# UPS_Module.net
KiCad netlist of a schematic drawn in Altium Designer
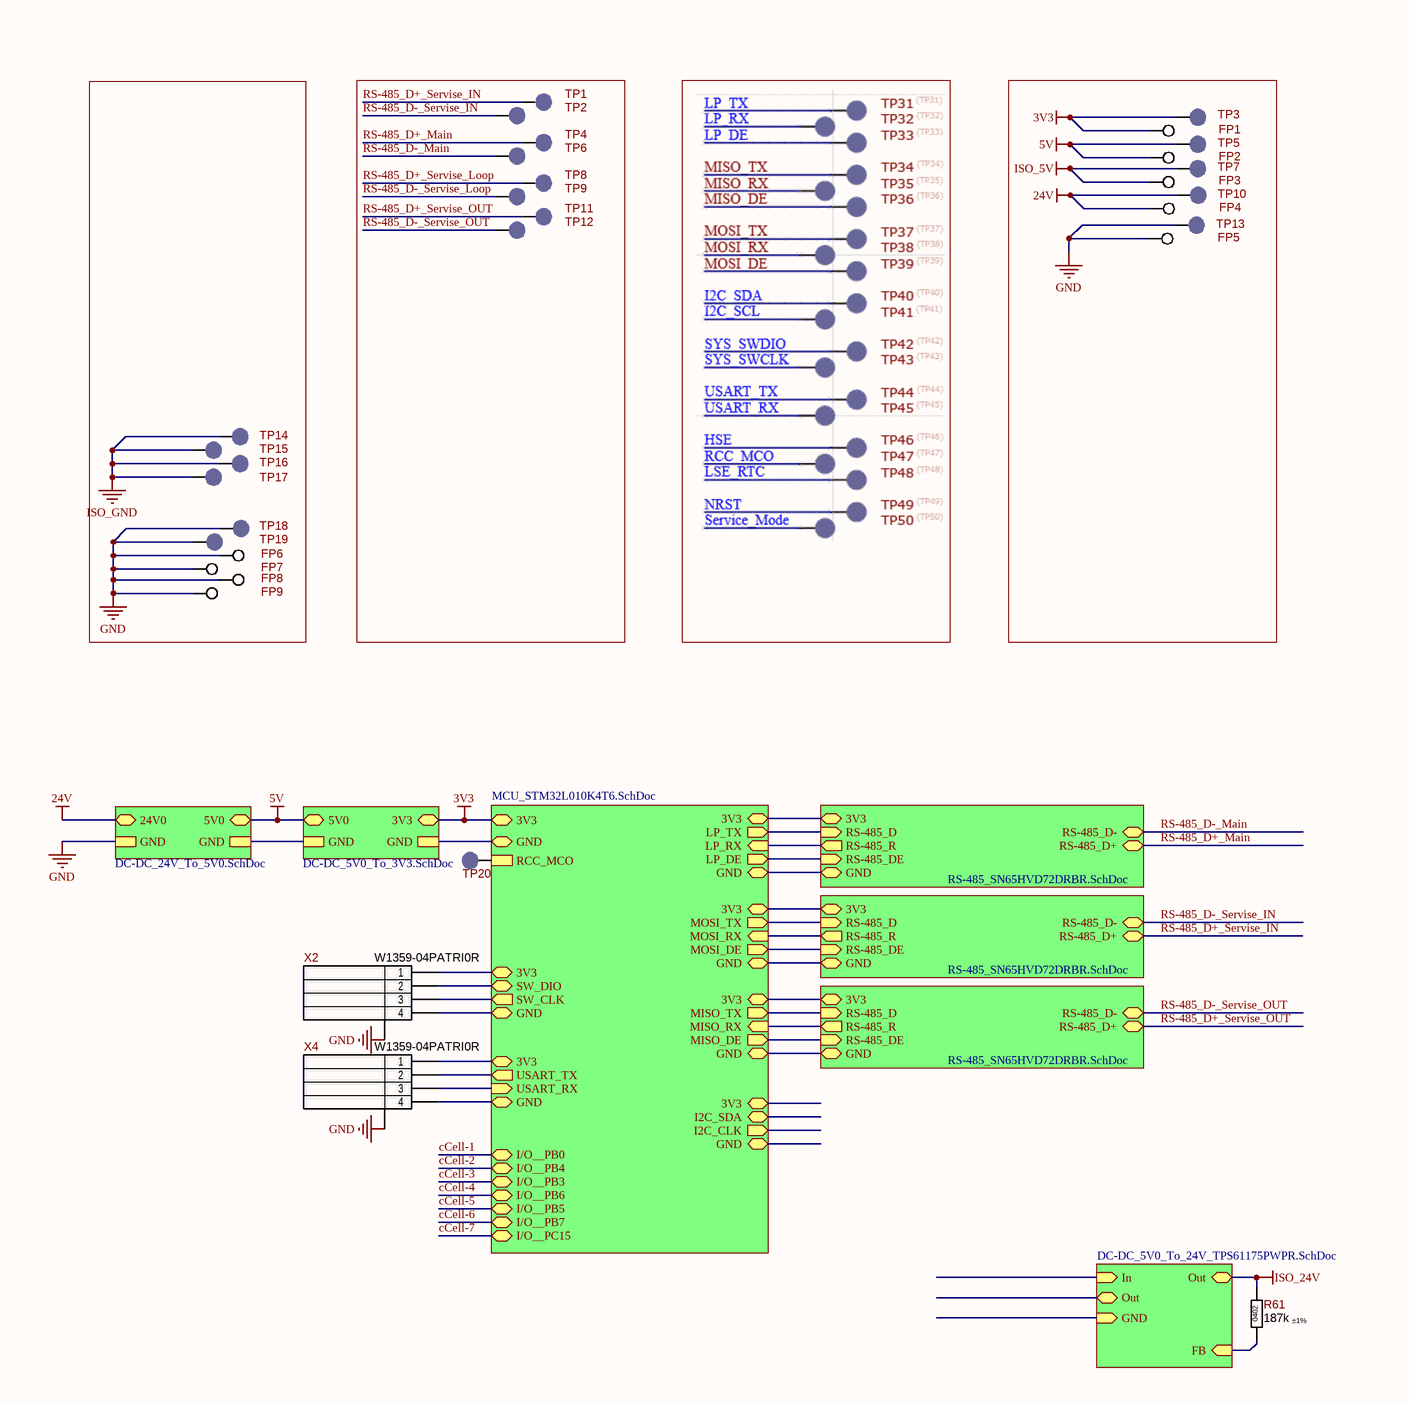
[diagram p0: UPS_Module.SchDoc, left]
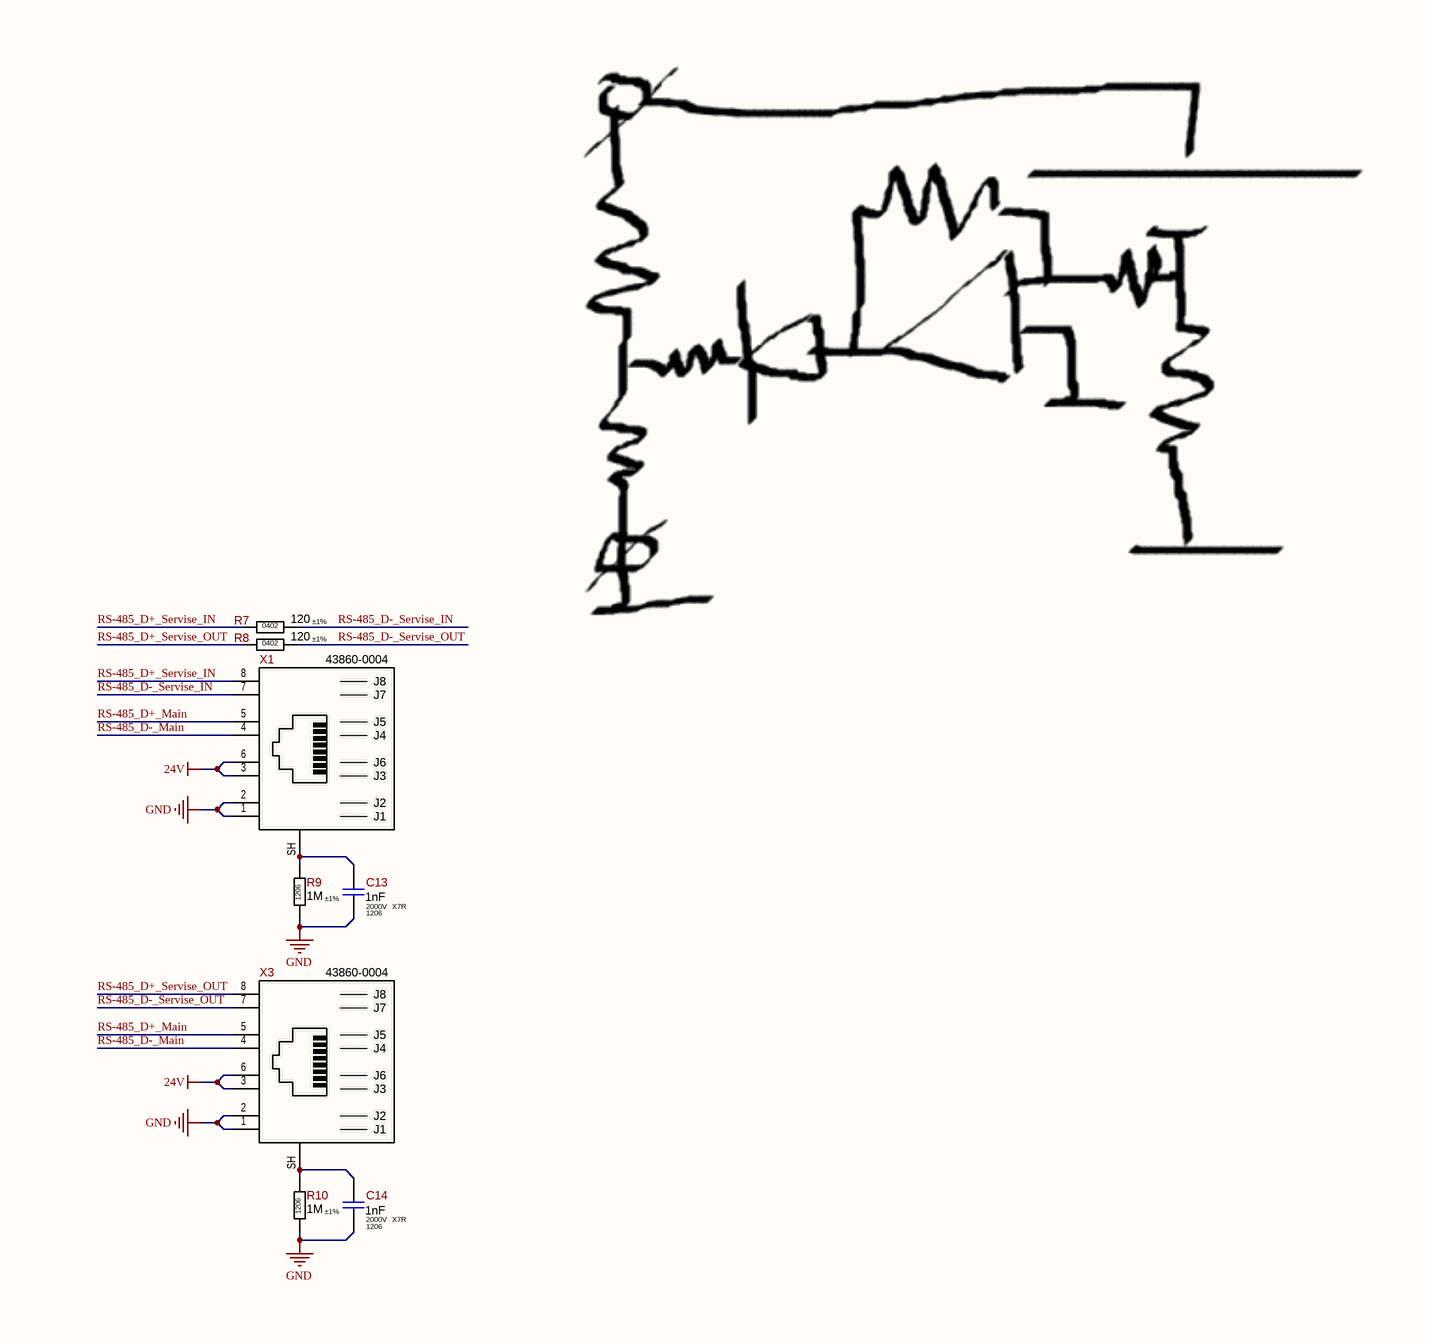
[diagram p1: UPS_Module.SchDoc, right]

(export (version "E")
  (design (tool "Eeschema 10.0.6"))
  (components
    (comp (ref "C13")
      (value "1nF")
      (footprint "CAP-1206(3216)X125T20")
      (description "1nF 2000V X7R ±10% 1206 Ceramic Capacitor RoHS")
      (fields
        (field (name "PACKAGE") "1206")
        (field (name "VOLTAGE") "2000V")
        (field (name "DIELECTRIC TYPE") "X7R")
        (field (name "PART NUMBER") "CC1206KKX7RDBB102")
        (field (name "MANUFACTURER") "Yageo")
      )
      (libsource (lib "EL.XXX.T01") (part "Capacitor-NonPolar"))
    )
    (comp (ref "C14")
      (value "1nF")
      (footprint "CAP-1206(3216)X125T20")
      (description "1nF 2000V X7R ±10% 1206 Ceramic Capacitor RoHS")
      (fields
        (field (name "PACKAGE") "1206")
        (field (name "VOLTAGE") "2000V")
        (field (name "DIELECTRIC TYPE") "X7R")
        (field (name "PART NUMBER") "CC1206KKX7RDBB102")
        (field (name "MANUFACTURER") "Yageo")
      )
      (libsource (lib "EL.XXX.T01") (part "Capacitor-NonPolar"))
    )
    (comp (ref "FP1")
      (value "PAD-1.1mm")
      (footprint "PAD-1.1mm")
      (description "1.1mm Pad for Plug-In or Receptacle")
      (fields (field (name "MANUFACTURER") "NONE"))
      (libsource (lib "EL.XXX.T01") (part "Pad"))
    )
    (comp (ref "FP2")
      (value "PAD-1.1mm")
      (footprint "PAD-1.1mm")
      (description "1.1mm Pad for Plug-In or Receptacle")
      (fields (field (name "MANUFACTURER") "NONE"))
      (libsource (lib "EL.XXX.T01") (part "Pad"))
    )
    (comp (ref "FP3")
      (value "PAD-1.1mm")
      (footprint "PAD-1.1mm")
      (description "1.1mm Pad for Plug-In or Receptacle")
      (fields (field (name "MANUFACTURER") "NONE"))
      (libsource (lib "EL.XXX.T01") (part "Pad"))
    )
    (comp (ref "FP4")
      (value "PAD-1.1mm")
      (footprint "PAD-1.1mm")
      (description "1.1mm Pad for Plug-In or Receptacle")
      (fields (field (name "MANUFACTURER") "NONE"))
      (libsource (lib "EL.XXX.T01") (part "Pad"))
    )
    (comp (ref "FP5")
      (value "PAD-1.1mm")
      (footprint "PAD-1.1mm")
      (description "1.1mm Pad for Plug-In or Receptacle")
      (fields (field (name "MANUFACTURER") "NONE"))
      (libsource (lib "EL.XXX.T01") (part "Pad"))
    )
    (comp (ref "FP6")
      (value "PAD-1.1mm")
      (footprint "PAD-1.1mm")
      (description "1.1mm Pad for Plug-In or Receptacle")
      (fields (field (name "MANUFACTURER") "NONE"))
      (libsource (lib "EL.XXX.T01") (part "Pad"))
    )
    (comp (ref "FP7")
      (value "PAD-1.1mm")
      (footprint "PAD-1.1mm")
      (description "1.1mm Pad for Plug-In or Receptacle")
      (fields (field (name "MANUFACTURER") "NONE"))
      (libsource (lib "EL.XXX.T01") (part "Pad"))
    )
    (comp (ref "FP8")
      (value "PAD-1.1mm")
      (footprint "PAD-1.1mm")
      (description "1.1mm Pad for Plug-In or Receptacle")
      (fields (field (name "MANUFACTURER") "NONE"))
      (libsource (lib "EL.XXX.T01") (part "Pad"))
    )
    (comp (ref "FP9")
      (value "PAD-1.1mm")
      (footprint "PAD-1.1mm")
      (description "1.1mm Pad for Plug-In or Receptacle")
      (fields (field (name "MANUFACTURER") "NONE"))
      (libsource (lib "EL.XXX.T01") (part "Pad"))
    )
    (comp (ref "R7")
      (value "120")
      (footprint "R_ANY_CHIP_0402_HI")
      (description "120 Ohms ±1% 1/16W 0402 Thick Film Resistor")
      (fields
        (field (name "TOLERANCE") "±1%")
        (field (name "PACKAGE") "0402")
        (field (name "PART NUMBER") "RC0402FR-07120RL")
        (field (name "MANUFACTURER") "Yageo")
      )
      (libsource (lib "EL.XXX.T01") (part "Resistor"))
    )
    (comp (ref "R8")
      (value "120")
      (footprint "R_ANY_CHIP_0402_HI")
      (description "120 Ohms ±1% 1/16W 0402 Thick Film Resistor")
      (fields
        (field (name "TOLERANCE") "±1%")
        (field (name "PACKAGE") "0402")
        (field (name "PART NUMBER") "RC0402FR-07120RL")
        (field (name "MANUFACTURER") "Yageo")
      )
      (libsource (lib "EL.XXX.T01") (part "Resistor"))
    )
    (comp (ref "R9")
      (value "1M")
      (footprint "CHV1206-Series")
      (description "1 MOhms ±1%, 1/4W 1206 Thick Film Resistor")
      (fields
        (field (name "TOLERANCE") "±1%")
        (field (name "PACKAGE") "1206")
        (field (name "PART NUMBER") "CHV1206-FX-1004ELF")
        (field (name "MANUFACTURER") "Bourns")
      )
      (libsource (lib "EL.XXX.T01") (part "Resistor"))
    )
    (comp (ref "R10")
      (value "1M")
      (footprint "CHV1206-Series")
      (description "1 MOhms ±1%, 1/4W 1206 Thick Film Resistor")
      (fields
        (field (name "TOLERANCE") "±1%")
        (field (name "PACKAGE") "1206")
        (field (name "PART NUMBER") "CHV1206-FX-1004ELF")
        (field (name "MANUFACTURER") "Bourns")
      )
      (libsource (lib "EL.XXX.T01") (part "Resistor"))
    )
    (comp (ref "R61")
      (value "187k")
      (footprint "R_ANY_CHIP_0402_MED")
      (description "187 kOhms ±1% 1/16W 0402 Thick Film Resistor")
      (fields
        (field (name "TOLERANCE") "±1%")
        (field (name "PACKAGE") "0402")
        (field (name "PART NUMBER") "RC0402FR-07187KL")
        (field (name "MANUFACTURER") "Yageo")
      )
      (libsource (lib "EL.XXX.T01") (part "Resistor"))
    )
    (comp (ref "TP1")
      (value "LED_LINK")
      (footprint "TP_SMD_2mm")
      (description "Test Point SMD Pad 1.0mm/1.5mm/2mm")
      (fields (field (name "PART NUMBER") "TP-PAD-SMD"))
      (libsource (lib "EL.XXX.T01") (part "Test-Point-SMD-1"))
    )
    (comp (ref "TP2")
      (value "LED_LINK")
      (footprint "TP_SMD_2mm")
      (description "Test Point SMD Pad 1.0mm/1.5mm/2mm")
      (fields (field (name "PART NUMBER") "TP-PAD-SMD"))
      (libsource (lib "EL.XXX.T01") (part "Test-Point-SMD-1"))
    )
    (comp (ref "TP3")
      (value "LED_LINK")
      (footprint "TP_SMD_2mm")
      (description "Test Point SMD Pad 1.0mm/1.5mm/2mm")
      (fields (field (name "PART NUMBER") "TP-PAD-SMD"))
      (libsource (lib "EL.XXX.T01") (part "Test-Point-SMD-1"))
    )
    (comp (ref "TP4")
      (value "LED_LINK")
      (footprint "TP_SMD_2mm")
      (description "Test Point SMD Pad 1.0mm/1.5mm/2mm")
      (fields (field (name "PART NUMBER") "TP-PAD-SMD"))
      (libsource (lib "EL.XXX.T01") (part "Test-Point-SMD-1"))
    )
    (comp (ref "TP5")
      (value "LED_LINK")
      (footprint "TP_SMD_2mm")
      (description "Test Point SMD Pad 1.0mm/1.5mm/2mm")
      (fields (field (name "PART NUMBER") "TP-PAD-SMD"))
      (libsource (lib "EL.XXX.T01") (part "Test-Point-SMD-1"))
    )
    (comp (ref "TP6")
      (value "LED_LINK")
      (footprint "TP_SMD_2mm")
      (description "Test Point SMD Pad 1.0mm/1.5mm/2mm")
      (fields (field (name "PART NUMBER") "TP-PAD-SMD"))
      (libsource (lib "EL.XXX.T01") (part "Test-Point-SMD-1"))
    )
    (comp (ref "TP7")
      (value "LED_LINK")
      (footprint "TP_SMD_2mm")
      (description "Test Point SMD Pad 1.0mm/1.5mm/2mm")
      (fields (field (name "PART NUMBER") "TP-PAD-SMD"))
      (libsource (lib "EL.XXX.T01") (part "Test-Point-SMD-1"))
    )
    (comp (ref "TP8")
      (value "LED_LINK")
      (footprint "TP_SMD_2mm")
      (description "Test Point SMD Pad 1.0mm/1.5mm/2mm")
      (fields (field (name "PART NUMBER") "TP-PAD-SMD"))
      (libsource (lib "EL.XXX.T01") (part "Test-Point-SMD-1"))
    )
    (comp (ref "TP9")
      (value "LED_LINK")
      (footprint "TP_SMD_2mm")
      (description "Test Point SMD Pad 1.0mm/1.5mm/2mm")
      (fields (field (name "PART NUMBER") "TP-PAD-SMD"))
      (libsource (lib "EL.XXX.T01") (part "Test-Point-SMD-1"))
    )
    (comp (ref "TP10")
      (value "LED_LINK")
      (footprint "TP_SMD_2mm")
      (description "Test Point SMD Pad 1.0mm/1.5mm/2mm")
      (fields (field (name "PART NUMBER") "TP-PAD-SMD"))
      (libsource (lib "EL.XXX.T01") (part "Test-Point-SMD-1"))
    )
    (comp (ref "TP11")
      (value "LED_LINK")
      (footprint "TP_SMD_2mm")
      (description "Test Point SMD Pad 1.0mm/1.5mm/2mm")
      (fields (field (name "PART NUMBER") "TP-PAD-SMD"))
      (libsource (lib "EL.XXX.T01") (part "Test-Point-SMD-1"))
    )
    (comp (ref "TP12")
      (value "LED_LINK")
      (footprint "TP_SMD_2mm")
      (description "Test Point SMD Pad 1.0mm/1.5mm/2mm")
      (fields (field (name "PART NUMBER") "TP-PAD-SMD"))
      (libsource (lib "EL.XXX.T01") (part "Test-Point-SMD-1"))
    )
    (comp (ref "TP13")
      (value "LED_LINK")
      (footprint "TP_SMD_2mm")
      (description "Test Point SMD Pad 1.0mm/1.5mm/2mm")
      (fields (field (name "PART NUMBER") "TP-PAD-SMD"))
      (libsource (lib "EL.XXX.T01") (part "Test-Point-SMD-1"))
    )
    (comp (ref "TP14")
      (value "LED_LINK")
      (footprint "TP_SMD_2mm")
      (description "Test Point SMD Pad 1.0mm/1.5mm/2mm")
      (fields (field (name "PART NUMBER") "TP-PAD-SMD"))
      (libsource (lib "EL.XXX.T01") (part "Test-Point-SMD-1"))
    )
    (comp (ref "TP15")
      (value "LED_LINK")
      (footprint "TP_SMD_2mm")
      (description "Test Point SMD Pad 1.0mm/1.5mm/2mm")
      (fields (field (name "PART NUMBER") "TP-PAD-SMD"))
      (libsource (lib "EL.XXX.T01") (part "Test-Point-SMD-1"))
    )
    (comp (ref "TP16")
      (value "LED_LINK")
      (footprint "TP_SMD_2mm")
      (description "Test Point SMD Pad 1.0mm/1.5mm/2mm")
      (fields (field (name "PART NUMBER") "TP-PAD-SMD"))
      (libsource (lib "EL.XXX.T01") (part "Test-Point-SMD-1"))
    )
    (comp (ref "TP17")
      (value "LED_LINK")
      (footprint "TP_SMD_2mm")
      (description "Test Point SMD Pad 1.0mm/1.5mm/2mm")
      (fields (field (name "PART NUMBER") "TP-PAD-SMD"))
      (libsource (lib "EL.XXX.T01") (part "Test-Point-SMD-1"))
    )
    (comp (ref "TP18")
      (value "LED_LINK")
      (footprint "TP_SMD_2mm")
      (description "Test Point SMD Pad 1.0mm/1.5mm/2mm")
      (fields (field (name "PART NUMBER") "TP-PAD-SMD"))
      (libsource (lib "EL.XXX.T01") (part "Test-Point-SMD-1"))
    )
    (comp (ref "TP19")
      (value "LED_LINK")
      (footprint "TP_SMD_2mm")
      (description "Test Point SMD Pad 1.0mm/1.5mm/2mm")
      (fields (field (name "PART NUMBER") "TP-PAD-SMD"))
      (libsource (lib "EL.XXX.T01") (part "Test-Point-SMD-1"))
    )
    (comp (ref "TP20")
      (value "LED_LINK")
      (footprint "TP_SMD_2mm")
      (description "Test Point SMD Pad 1.0mm/1.5mm/2mm")
      (fields (field (name "PART NUMBER") "TP-PAD-SMD"))
      (libsource (lib "EL.XXX.T01") (part "Test-Point-SMD-1"))
    )
    (comp (ref "X1")
      (value "43860-0004")
      (footprint "43860-0004")
      (description "RJ45 8P8C Shielded Cat 3 10 Base-T Connector")
      (fields (field (name "PART NUMBER") "43860-0004") (field (name "MANUFACTURER") "Molex"))
      (libsource (lib "EL.XXX.T01") (part "43860-0004"))
    )
    (comp (ref "X2")
      (value "W1359-04PATRI0R")
      (footprint "W1359-04PATXI0R_DBG")
      (description "1.25mm Wire-to-Board Header, Vertical, SMT, 4 pin")
      (fields
        (field (name "PART NUMBER") "W1359-04PATRI0R")
        (field (name "MANUFACTURER") "Hsuan Mao Technology")
      )
      (libsource (lib "EL.XXX.T01") (part "General-4-Pin-MP"))
    )
    (comp (ref "X3")
      (value "43860-0004")
      (footprint "43860-0004")
      (description "RJ45 8P8C Shielded Cat 3 10 Base-T Connector")
      (fields (field (name "PART NUMBER") "43860-0004") (field (name "MANUFACTURER") "Molex"))
      (libsource (lib "EL.XXX.T01") (part "43860-0004"))
    )
    (comp (ref "X4")
      (value "W1359-04PATRI0R")
      (footprint "W1359-04PATXI0R_DBG")
      (description "1.25mm Wire-to-Board Header, Vertical, SMT, 4 pin")
      (fields
        (field (name "PART NUMBER") "W1359-04PATRI0R")
        (field (name "MANUFACTURER") "Hsuan Mao Technology")
      )
      (libsource (lib "EL.XXX.T01") (part "General-4-Pin-MP"))
    )
  )
  (nets
    (net (code "4") (name "/3V3_3") (class "Default")
      (node (ref "X2") (pin "1") (pinfunction "1_1") (pintype "passive"))
    )
    (net (code "6") (name "/3V3_5") (class "Default")
      (node (ref "X4") (pin "1") (pinfunction "1_1") (pintype "passive"))
    )
    (net (code "10") (name "/FB") (class "Default") (node (ref "R61") (pin "2") (pintype "passive")))
    (net (code "15") (name "/GND_4") (class "Default")
      (node (ref "X4") (pin "4") (pinfunction "4_4") (pintype "passive"))
    )
    (net (code "20") (name "/GND_9") (class "Default")
      (node (ref "X2") (pin "4") (pinfunction "4_4") (pintype "passive"))
    )
    (net (code "36") (name "/RCC_MCO") (class "Default") (node (ref "TP20") (pin "1") (pintype "passive")))
    (net (code "38") (name "/RS-485_D+_Main") (class "Default")
      (node (ref "TP4") (pin "1") (pintype "passive"))
      (node (ref "X1") (pin "5") (pinfunction "CT_5") (pintype "passive"))
      (node (ref "X3") (pin "5") (pinfunction "CT_5") (pintype "passive"))
    )
    (net (code "39") (name "/RS-485_D+_Servise_IN") (class "Default")
      (node (ref "R7") (pin "1") (pintype "passive"))
      (node (ref "TP1") (pin "1") (pintype "passive"))
      (node (ref "X1") (pin "8") (pinfunction "TD2+_8") (pintype "passive"))
    )
    (net (code "40") (name "/RS-485_D+_Servise_Loop") (class "Default")
      (node (ref "TP8") (pin "1") (pintype "passive"))
    )
    (net (code "41") (name "/RS-485_D+_Servise_OUT") (class "Default")
      (node (ref "R8") (pin "1") (pintype "passive"))
      (node (ref "TP11") (pin "1") (pintype "passive"))
      (node (ref "X3") (pin "8") (pinfunction "TD2+_8") (pintype "passive"))
    )
    (net (code "42") (name "/RS-485_D-_Main") (class "Default")
      (node (ref "TP6") (pin "1") (pintype "passive"))
      (node (ref "X1") (pin "4") (pinfunction "TD3+_4") (pintype "passive"))
      (node (ref "X3") (pin "4") (pinfunction "TD3+_4") (pintype "passive"))
    )
    (net (code "43") (name "/RS-485_D-_Servise_IN") (class "Default")
      (node (ref "R7") (pin "2") (pintype "passive"))
      (node (ref "TP2") (pin "1") (pintype "passive"))
      (node (ref "X1") (pin "7") (pinfunction "TD2-_7") (pintype "passive"))
    )
    (net (code "44") (name "/RS-485_D-_Servise_Loop") (class "Default")
      (node (ref "TP9") (pin "1") (pintype "passive"))
    )
    (net (code "45") (name "/RS-485_D-_Servise_OUT") (class "Default")
      (node (ref "R8") (pin "2") (pintype "passive"))
      (node (ref "TP12") (pin "1") (pintype "passive"))
      (node (ref "X3") (pin "7") (pinfunction "TD2-_7") (pintype "passive"))
    )
    (net (code "54") (name "/SW_CLK") (class "Default")
      (node (ref "X2") (pin "3") (pinfunction "3_3") (pintype "passive"))
    )
    (net (code "55") (name "/SW_DIO") (class "Default")
      (node (ref "X2") (pin "2") (pinfunction "2_2") (pintype "passive"))
    )
    (net (code "56") (name "/USART_RX") (class "Default")
      (node (ref "X4") (pin "3") (pinfunction "3_3") (pintype "passive"))
    )
    (net (code "57") (name "/USART_TX") (class "Default")
      (node (ref "X4") (pin "2") (pinfunction "2_2") (pintype "passive"))
    )
    (net (code "65") (name "3V3") (class "Default")
      (node (ref "FP1") (pin "1") (pintype "passive"))
      (node (ref "TP3") (pin "1") (pintype "passive"))
    )
    (net (code "66") (name "5V") (class "Default")
      (node (ref "FP2") (pin "1") (pintype "passive"))
      (node (ref "TP5") (pin "1") (pintype "passive"))
    )
    (net (code "67") (name "24V") (class "Default")
      (node (ref "FP4") (pin "1") (pintype "passive"))
      (node (ref "TP10") (pin "1") (pintype "passive"))
      (node (ref "X1") (pin "3") (pinfunction "TD3-_3") (pintype "passive"))
      (node (ref "X1") (pin "6") (pinfunction "CT_6") (pintype "passive"))
      (node (ref "X3") (pin "3") (pinfunction "TD3-_3") (pintype "passive"))
      (node (ref "X3") (pin "6") (pinfunction "CT_6") (pintype "passive"))
    )
    (net (code "68") (name "GND") (class "Default")
      (node (ref "C13") (pin "2") (pinfunction "2_2") (pintype "passive"))
      (node (ref "C14") (pin "2") (pinfunction "2_2") (pintype "passive"))
      (node (ref "FP5") (pin "1") (pintype "passive"))
      (node (ref "FP6") (pin "1") (pintype "passive"))
      (node (ref "FP7") (pin "1") (pintype "passive"))
      (node (ref "FP8") (pin "1") (pintype "passive"))
      (node (ref "FP9") (pin "1") (pintype "passive"))
      (node (ref "R10") (pin "2") (pintype "passive"))
      (node (ref "R9") (pin "2") (pintype "passive"))
      (node (ref "TP13") (pin "1") (pintype "passive"))
      (node (ref "TP18") (pin "1") (pintype "passive"))
      (node (ref "TP19") (pin "1") (pintype "passive"))
      (node (ref "X1") (pin "1") (pinfunction "TD4-_1") (pintype "passive"))
      (node (ref "X1") (pin "2") (pinfunction "TD4+_2") (pintype "passive"))
      (node (ref "X2") (pin "MP") (pinfunction "MountPad_MP") (pintype "passive"))
      (node (ref "X3") (pin "1") (pinfunction "TD4-_1") (pintype "passive"))
      (node (ref "X3") (pin "2") (pinfunction "TD4+_2") (pintype "passive"))
      (node (ref "X4") (pin "MP") (pinfunction "MountPad_MP") (pintype "passive"))
    )
    (net (code "69") (name "ISO_5V") (class "Default")
      (node (ref "FP3") (pin "1") (pintype "passive"))
      (node (ref "TP7") (pin "1") (pintype "passive"))
    )
    (net (code "70") (name "ISO_24V") (class "Default") (node (ref "R61") (pin "1") (pintype "passive")))
    (net (code "71") (name "ISO_GND") (class "Default")
      (node (ref "TP14") (pin "1") (pintype "passive"))
      (node (ref "TP15") (pin "1") (pintype "passive"))
      (node (ref "TP16") (pin "1") (pintype "passive"))
      (node (ref "TP17") (pin "1") (pintype "passive"))
    )
    (net (code "72") (name "Net-(X1-Shield)") (class "Default")
      (node (ref "C13") (pin "1") (pinfunction "1_1") (pintype "passive"))
      (node (ref "R9") (pin "1") (pintype "passive"))
      (node (ref "X1") (pin "SH") (pinfunction "Shield_SH") (pintype "passive"))
    )
    (net (code "73") (name "Net-(X3-Shield)") (class "Default")
      (node (ref "C14") (pin "1") (pinfunction "1_1") (pintype "passive"))
      (node (ref "R10") (pin "1") (pintype "passive"))
      (node (ref "X3") (pin "SH") (pinfunction "Shield_SH") (pintype "passive"))
    )
  )
)
